# OpenBook_Reader_schematic.net
KiCad netlist of a schematic drawn in EAGLE
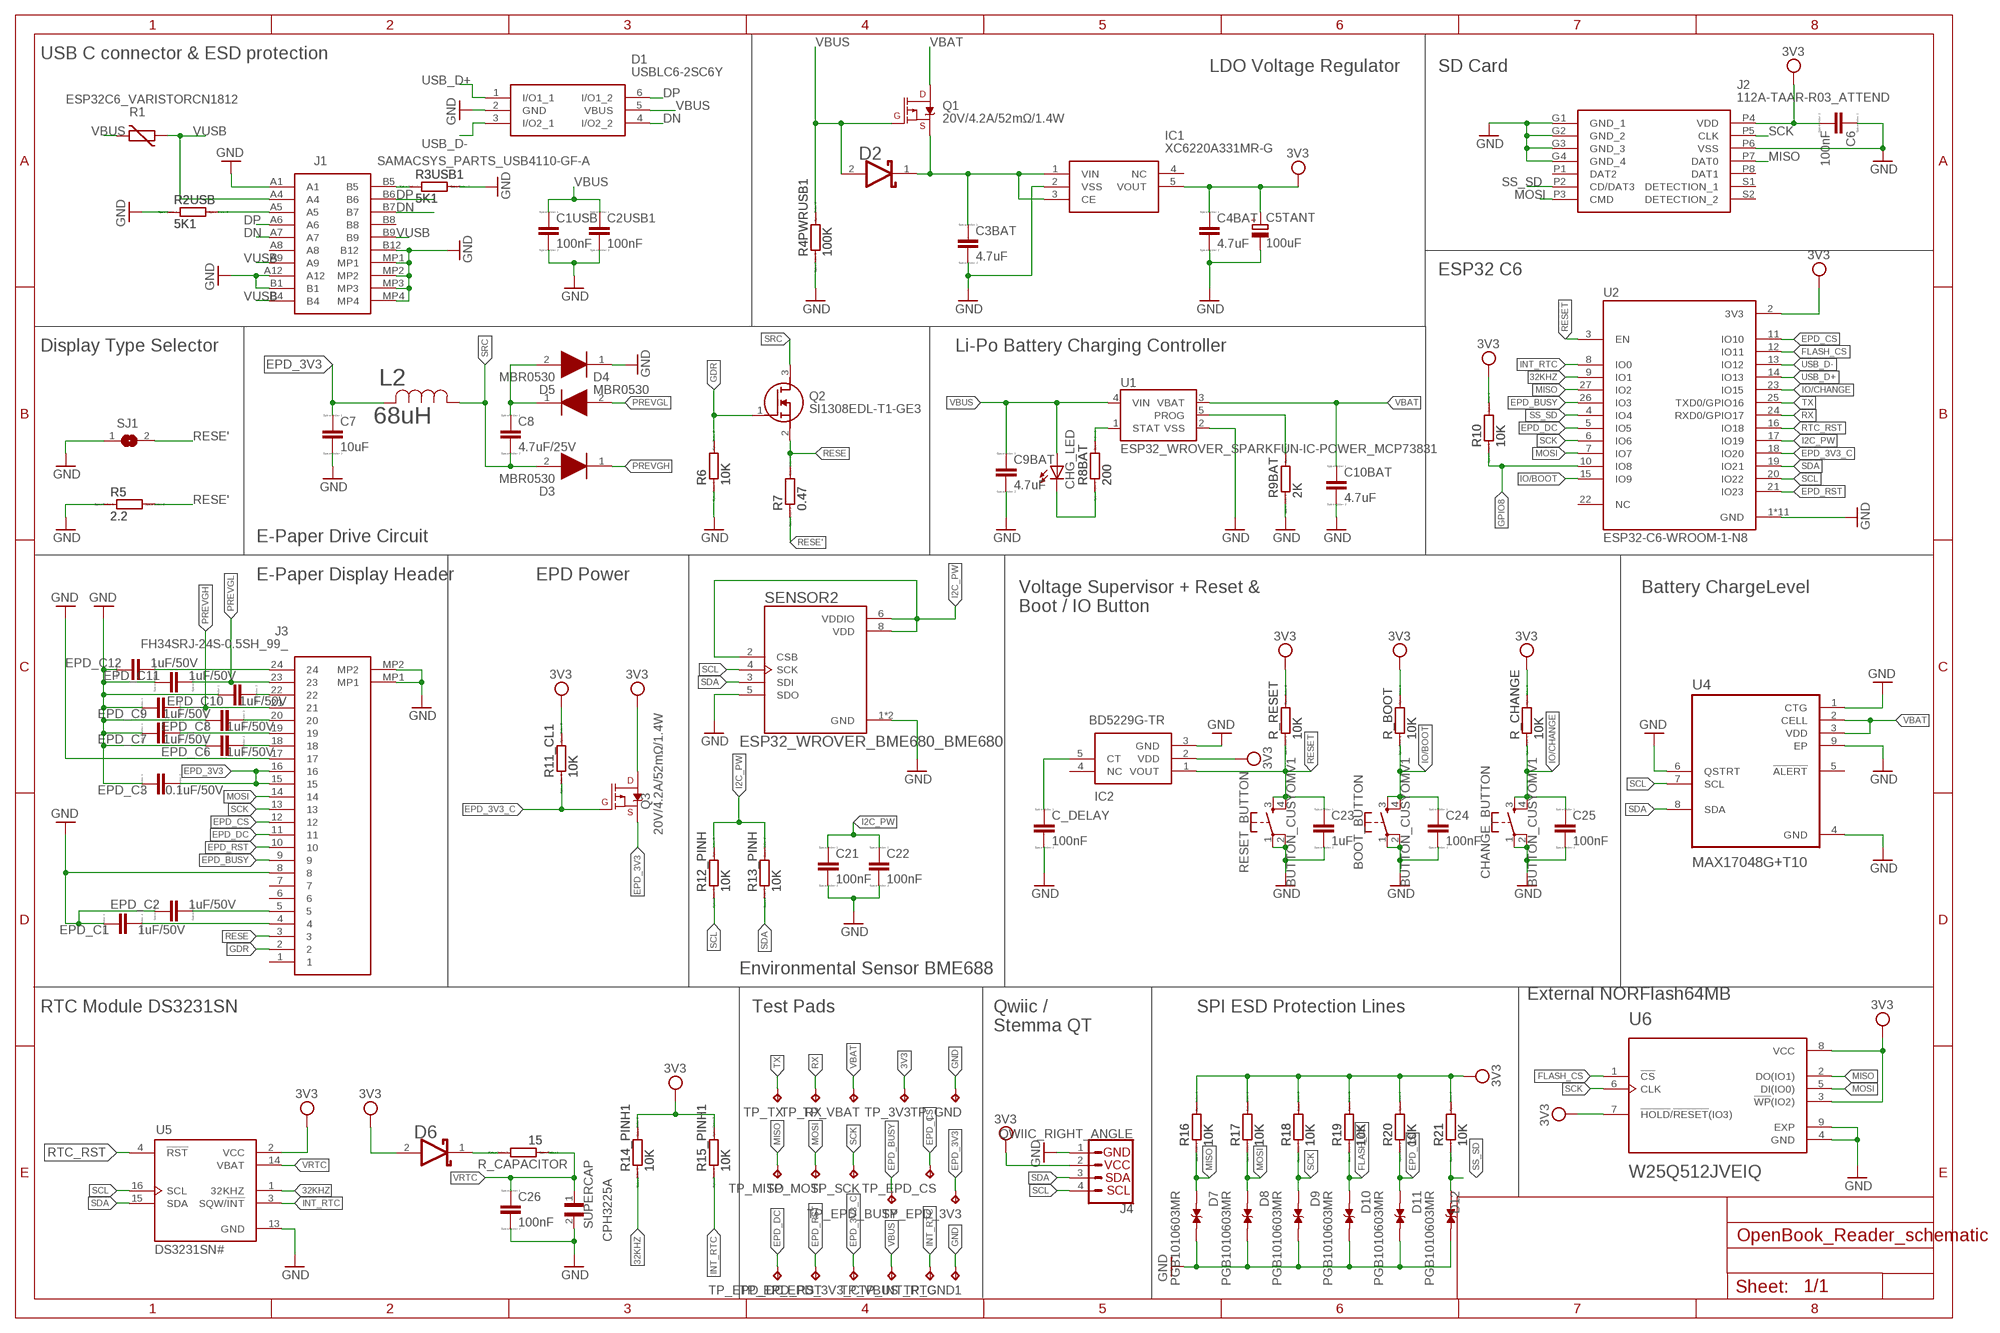
[diagram p0: schematic, sheet 1]

(export (version "E")
  (design (tool "Eeschema 10.0.6"))
  (components
    (comp (ref "BOOT_BUTTON")
      (value "BUTTON_CUSYOMV1")
      (footprint "eagle-import:MYBUTTON")
      (libsource (lib "eagle-import") (part "BUTTON_CUSYOMV1"))
    )
    (comp (ref "C1USB")
      (value "100nF")
      (footprint "eagle-import:ESP32_WROVER_EAGLE-LTSPICE_C0402")
      (libsource (lib "eagle-import") (part "EAGLE-LTSPICE_CC0402"))
    )
    (comp (ref "C2USB1")
      (value "100nF")
      (footprint "eagle-import:ESP32_WROVER_EAGLE-LTSPICE_C0402")
      (libsource (lib "eagle-import") (part "EAGLE-LTSPICE_CC0402"))
    )
    (comp (ref "C3BAT")
      (value "4.7uF")
      (footprint "eagle-import:ESP32_WROVER_EAGLE-LTSPICE_C0402")
      (libsource (lib "eagle-import") (part "EAGLE-LTSPICE_CC0402"))
    )
    (comp (ref "C4BAT")
      (value "4.7uF")
      (footprint "eagle-import:ESP32_WROVER_EAGLE-LTSPICE_C0402")
      (libsource (lib "eagle-import") (part "EAGLE-LTSPICE_CC0402"))
    )
    (comp (ref "C5TANT")
      (value "100uF")
      (footprint "eagle-import:RCL_CT3528")
      (libsource (lib "eagle-import") (part "RCL_CPOL-EUCT3528"))
    )
    (comp (ref "C6")
      (value "100nF")
      (footprint "eagle-import:ESP32_WROVER_EAGLE-LTSPICE_C0402")
      (libsource (lib "eagle-import") (part "EAGLE-LTSPICE_CC0402"))
    )
    (comp (ref "C7")
      (value "10uF")
      (footprint "eagle-import:ESP32_WROVER_EAGLE-LTSPICE_C0402")
      (libsource (lib "eagle-import") (part "EAGLE-LTSPICE_CC0402"))
    )
    (comp (ref "C8")
      (value "4.7uF/25V")
      (footprint "eagle-import:ESP32_WROVER_EAGLE-LTSPICE_C0402")
      (libsource (lib "eagle-import") (part "EAGLE-LTSPICE_CC0402"))
    )
    (comp (ref "C9BAT")
      (value "4.7uF")
      (footprint "eagle-import:ESP32_WROVER_EAGLE-LTSPICE_C0402")
      (libsource (lib "eagle-import") (part "EAGLE-LTSPICE_CC0402"))
    )
    (comp (ref "C10BAT")
      (value "4.7uF")
      (footprint "eagle-import:ESP32_WROVER_EAGLE-LTSPICE_C0402")
      (libsource (lib "eagle-import") (part "EAGLE-LTSPICE_CC0402"))
    )
    (comp (ref "C21")
      (value "100nF")
      (footprint "eagle-import:ESP32_WROVER_EAGLE-LTSPICE_C0402")
      (libsource (lib "eagle-import") (part "EAGLE-LTSPICE_CC0402"))
    )
    (comp (ref "C22")
      (value "100nF")
      (footprint "eagle-import:ESP32_WROVER_EAGLE-LTSPICE_C0402")
      (libsource (lib "eagle-import") (part "EAGLE-LTSPICE_CC0402"))
    )
    (comp (ref "C23")
      (value "1uF")
      (footprint "eagle-import:ESP32_WROVER_EAGLE-LTSPICE_C0402")
      (libsource (lib "eagle-import") (part "EAGLE-LTSPICE_CC0402"))
    )
    (comp (ref "C24")
      (value "100nF")
      (footprint "eagle-import:ESP32_WROVER_EAGLE-LTSPICE_C0402")
      (libsource (lib "eagle-import") (part "EAGLE-LTSPICE_CC0402"))
    )
    (comp (ref "C25")
      (value "100nF")
      (footprint "eagle-import:ESP32_WROVER_EAGLE-LTSPICE_C0402")
      (libsource (lib "eagle-import") (part "EAGLE-LTSPICE_CC0402"))
    )
    (comp (ref "C26")
      (value "100nF")
      (footprint "eagle-import:ESP32_WROVER_EAGLE-LTSPICE_C0402")
      (libsource (lib "eagle-import") (part "EAGLE-LTSPICE_CC0402"))
    )
    (comp (ref "CHANGE_BUTTON")
      (value "BUTTON_CUSYOMV1")
      (footprint "eagle-import:MYBUTTON")
      (libsource (lib "eagle-import") (part "BUTTON_CUSYOMV1"))
    )
    (comp (ref "CHG_LED")
      (value "ADAFRUIT_LEDCHIP-LED0603")
      (footprint "eagle-import:ADAFRUIT_CHIP-LED0603")
      (libsource (lib "eagle-import") (part "ADAFRUIT_LEDCHIP-LED0603"))
    )
    (comp (ref "C_DELAY")
      (value "100nF")
      (footprint "eagle-import:ESP32_WROVER_EAGLE-LTSPICE_C0402")
      (libsource (lib "eagle-import") (part "EAGLE-LTSPICE_CC0402"))
    )
    (comp (ref "D1")
      (value "USBLC6-2SC6Y")
      (footprint "eagle-import:SOT95P280X145-6N")
      (fields (field (name "MF") "STMicroelectronics"))
      (libsource (lib "eagle-import") (part "USBLC6-2SC6Y"))
    )
    (comp (ref "D2")
      (value "ESP32_WROVER_AVX---SD0805S020S1R0_AVX_SD0805S020S1R0_0_0AVX_SD0805S020S1R0_0_0")
      (footprint "eagle-import:ESP32_WROVER_AVX---SD0805S020S1R0_AVX_SD0805S020S1R0_0")
      (fields
        (field (name "DIGIKEY_PART_NUMBER") "478-7800-1-ND")
        (field (name "MF") "AVX")
        (field (name "MOUSER_PART_NUMBER") "581-SD0805S020S1R0")
      )
      (libsource (lib "eagle-import") (part "ESP32_WROVER_AVX---SD0805S020S1R0_AVX_SD0805S020S1R0_0_0AVX_SD0805S020S1R0_0_0"))
    )
    (comp (ref "D3")
      (value "MBR0530")
      (footprint "eagle-import:SOD3716X135N")
      (fields (field (name "MF") "ON Semiconductor"))
      (libsource (lib "eagle-import") (part "MBR0530"))
    )
    (comp (ref "D4")
      (value "MBR0530")
      (footprint "eagle-import:SOD3716X135N")
      (fields (field (name "MF") "ON Semiconductor"))
      (libsource (lib "eagle-import") (part "MBR0530"))
    )
    (comp (ref "D5")
      (value "MBR0530")
      (footprint "eagle-import:SOD3716X135N")
      (fields (field (name "MF") "ON Semiconductor"))
      (libsource (lib "eagle-import") (part "MBR0530"))
    )
    (comp (ref "D6")
      (value "ESP32_WROVER_AVX---SD0805S020S1R0_AVX_SD0805S020S1R0_0_0AVX_SD0805S020S1R0_0_0")
      (footprint "eagle-import:ESP32_WROVER_AVX---SD0805S020S1R0_AVX_SD0805S020S1R0_0")
      (fields
        (field (name "DIGIKEY_PART_NUMBER") "478-7800-1-ND")
        (field (name "MF") "AVX")
        (field (name "MOUSER_PART_NUMBER") "581-SD0805S020S1R0")
      )
      (libsource (lib "eagle-import") (part "ESP32_WROVER_AVX---SD0805S020S1R0_AVX_SD0805S020S1R0_0_0AVX_SD0805S020S1R0_0_0"))
    )
    (comp (ref "D7")
      (value "PGB1010603MR")
      (footprint "eagle-import:DIOC1608X36N")
      (fields (field (name "MF") "Littelfuse Inc."))
      (libsource (lib "eagle-import") (part "PGB1010603MR"))
    )
    (comp (ref "D8")
      (value "PGB1010603MR")
      (footprint "eagle-import:DIOC1608X36N")
      (fields (field (name "MF") "Littelfuse Inc."))
      (libsource (lib "eagle-import") (part "PGB1010603MR"))
    )
    (comp (ref "D9")
      (value "PGB1010603MR")
      (footprint "eagle-import:DIOC1608X36N")
      (fields (field (name "MF") "Littelfuse Inc."))
      (libsource (lib "eagle-import") (part "PGB1010603MR"))
    )
    (comp (ref "D10")
      (value "PGB1010603MR")
      (footprint "eagle-import:DIOC1608X36N")
      (fields (field (name "MF") "Littelfuse Inc."))
      (libsource (lib "eagle-import") (part "PGB1010603MR"))
    )
    (comp (ref "D11")
      (value "PGB1010603MR")
      (footprint "eagle-import:DIOC1608X36N")
      (fields (field (name "MF") "Littelfuse Inc."))
      (libsource (lib "eagle-import") (part "PGB1010603MR"))
    )
    (comp (ref "D12")
      (value "PGB1010603MR")
      (footprint "eagle-import:DIOC1608X36N")
      (fields (field (name "MF") "Littelfuse Inc."))
      (libsource (lib "eagle-import") (part "PGB1010603MR"))
    )
    (comp (ref "EPD_C1")
      (value "1uF/50V")
      (footprint "eagle-import:ESP32_WROVER_EAGLE-LTSPICE_C0402")
      (libsource (lib "eagle-import") (part "EAGLE-LTSPICE_CC0402"))
    )
    (comp (ref "EPD_C2")
      (value "1uF/50V")
      (footprint "eagle-import:ESP32_WROVER_EAGLE-LTSPICE_C0402")
      (libsource (lib "eagle-import") (part "EAGLE-LTSPICE_CC0402"))
    )
    (comp (ref "EPD_C3")
      (value "0.1uF/50V")
      (footprint "eagle-import:ESP32_WROVER_EAGLE-LTSPICE_C0402")
      (libsource (lib "eagle-import") (part "EAGLE-LTSPICE_CC0402"))
    )
    (comp (ref "EPD_C6")
      (value "1uF/50V")
      (footprint "eagle-import:ESP32_WROVER_EAGLE-LTSPICE_C0402")
      (libsource (lib "eagle-import") (part "EAGLE-LTSPICE_CC0402"))
    )
    (comp (ref "EPD_C7")
      (value "1uF/50V")
      (footprint "eagle-import:ESP32_WROVER_EAGLE-LTSPICE_C0402")
      (libsource (lib "eagle-import") (part "EAGLE-LTSPICE_CC0402"))
    )
    (comp (ref "EPD_C8")
      (value "1uF/50V")
      (footprint "eagle-import:ESP32_WROVER_EAGLE-LTSPICE_C0402")
      (libsource (lib "eagle-import") (part "EAGLE-LTSPICE_CC0402"))
    )
    (comp (ref "EPD_C9")
      (value "1uF/50V")
      (footprint "eagle-import:ESP32_WROVER_EAGLE-LTSPICE_C0402")
      (libsource (lib "eagle-import") (part "EAGLE-LTSPICE_CC0402"))
    )
    (comp (ref "EPD_C10")
      (value "1uF/50V")
      (footprint "eagle-import:ESP32_WROVER_EAGLE-LTSPICE_C0402")
      (libsource (lib "eagle-import") (part "EAGLE-LTSPICE_CC0402"))
    )
    (comp (ref "EPD_C11")
      (value "1uF/50V")
      (footprint "eagle-import:ESP32_WROVER_EAGLE-LTSPICE_C0402")
      (libsource (lib "eagle-import") (part "EAGLE-LTSPICE_CC0402"))
    )
    (comp (ref "EPD_C12")
      (value "1uF/50V")
      (footprint "eagle-import:ESP32_WROVER_EAGLE-LTSPICE_C0402")
      (libsource (lib "eagle-import") (part "EAGLE-LTSPICE_CC0402"))
    )
    (comp (ref "IC1")
      (value "XC6220A331MR-G")
      (footprint "eagle-import:SOT95P280X120-5N")
      (fields (field (name "MOUSER_PART_NUMBER") "865-XC6220A331MR-G"))
      (libsource (lib "eagle-import") (part "XC6220A331MR-G"))
    )
    (comp (ref "IC2")
      (value "BD5229G-TR")
      (footprint "eagle-import:SOT95P280X125-5N")
      (fields (field (name "MOUSER_PART_NUMBER") "755-BD5229G-TR"))
      (libsource (lib "eagle-import") (part "BD5229G-TR"))
    )
    (comp (ref "J1")
      (value "SAMACSYS_PARTS_USB4110-GF-A")
      (footprint "eagle-import:SAMACSYS_PARTS_USB4110GFA")
      (fields
        (field (name "MANUFACTURER_PART_NUMBER") "USB4110-GF-A")
        (field (name "MOUSER_PART_NUMBER") "640-USB4110-GF-A")
      )
      (libsource (lib "eagle-import") (part "SAMACSYS_PARTS_USB4110-GF-A"))
    )
    (comp (ref "J2")
      (value "112A-TAAR-R03_ATTEND")
      (footprint "eagle-import:112ATAARR03ATTEND")
      (fields (field (name "MANUFACTURER_PART_NUMBER") "112A-TAAR-R03 ATTEND"))
      (libsource (lib "eagle-import") (part "112A-TAAR-R03_ATTEND"))
    )
    (comp (ref "J3")
      (value "FH34SRJ-24S-0.5SH_99_")
      (footprint "eagle-import:FH34SRJ24S05SH99")
      (fields
        (field (name "MANUFACTURER_PART_NUMBER") "FH34SRJ-24S-0.5SH(99)")
        (field (name "MOUSER_PART_NUMBER") "798-FH34SRJ24S05SH99")
      )
      (libsource (lib "eagle-import") (part "FH34SRJ-24S-0.5SH_99_"))
    )
    (comp (ref "J4")
      (value "QWIIC_RIGHT_ANGLE")
      (footprint "eagle-import:JST04_1MM_RA")
      (libsource (lib "eagle-import") (part "QWIIC_CONNECTORJS-1MM"))
    )
    (comp (ref "L2")
      (value "68uH")
      (footprint "eagle-import:IND_4828-WE-TPC_WRE")
      (fields
        (field (name "MANUFACTURER_PART_NUMBER") "744043680")
        (field (name "COPYRIGHT") "Copyright (C) 2024 Ultra Librarian. All rights reserved.")
      )
      (libsource (lib "eagle-import") (part "744043680IND_4828-WE-TPC_WRE"))
    )
    (comp (ref "Q1")
      (value "20V/4.2A/52mΩ/1.4W")
      (footprint "eagle-import:ESP32_WROVER_SPARKFUN-DISCRETESEMI_SOT23-3")
      (libsource (lib "eagle-import") (part "ESP32_WROVER_SPARKFUN-DISCRETESEMI_MOSFET_PCH-DMG2305UX-7"))
    )
    (comp (ref "Q2")
      (value "SI1308EDL-T1-GE3")
      (footprint "eagle-import:SOT65P210X110-3N")
      (fields (field (name "MF") "Vishay Siliconix"))
      (libsource (lib "eagle-import") (part "SI1308EDL-T1-GE3"))
    )
    (comp (ref "Q3")
      (value "20V/4.2A/52mΩ/1.4W")
      (footprint "eagle-import:ESP32_WROVER_SPARKFUN-DISCRETESEMI_SOT23-3")
      (libsource (lib "eagle-import") (part "ESP32_WROVER_SPARKFUN-DISCRETESEMI_MOSFET_PCH-DMG2305UX-7"))
    )
    (comp (ref "R1")
      (value "ESP32C6_VARISTORCN1812")
      (footprint "eagle-import:ESP32C6_VARISTOR_CT_CN1812")
      (libsource (lib "eagle-import") (part "ESP32C6_VARISTORCN1812"))
    )
    (comp (ref "R2USB")
      (value "5K1")
      (footprint "eagle-import:ESP32_WROVER_EAGLE-LTSPICE_R0402")
      (libsource (lib "eagle-import") (part "ESP32_WROVER_EAGLE-LTSPICE_RR0402"))
    )
    (comp (ref "R3USB1")
      (value "5K1")
      (footprint "eagle-import:ESP32_WROVER_EAGLE-LTSPICE_R0402")
      (libsource (lib "eagle-import") (part "ESP32_WROVER_EAGLE-LTSPICE_RR0402"))
    )
    (comp (ref "R4PWRUSB1")
      (value "100K")
      (footprint "eagle-import:ESP32_WROVER_EAGLE-LTSPICE_R0402")
      (libsource (lib "eagle-import") (part "ESP32_WROVER_EAGLE-LTSPICE_RR0402"))
    )
    (comp (ref "R5")
      (value "2.2")
      (footprint "eagle-import:ESP32_WROVER_EAGLE-LTSPICE_R0402")
      (libsource (lib "eagle-import") (part "ESP32_WROVER_EAGLE-LTSPICE_RR0402"))
    )
    (comp (ref "R6")
      (value "10K")
      (footprint "eagle-import:ESP32_WROVER_EAGLE-LTSPICE_R0402")
      (libsource (lib "eagle-import") (part "ESP32_WROVER_EAGLE-LTSPICE_RR0402"))
    )
    (comp (ref "R7")
      (value "0.47")
      (footprint "eagle-import:ESP32_WROVER_EAGLE-LTSPICE_R0402")
      (libsource (lib "eagle-import") (part "ESP32_WROVER_EAGLE-LTSPICE_RR0402"))
    )
    (comp (ref "R8BAT")
      (value "200")
      (footprint "eagle-import:ESP32_WROVER_EAGLE-LTSPICE_R0402")
      (libsource (lib "eagle-import") (part "ESP32_WROVER_EAGLE-LTSPICE_RR0402"))
    )
    (comp (ref "R9BAT")
      (value "2K")
      (footprint "eagle-import:ESP32_WROVER_EAGLE-LTSPICE_R0402")
      (libsource (lib "eagle-import") (part "ESP32_WROVER_EAGLE-LTSPICE_RR0402"))
    )
    (comp (ref "R10")
      (value "10K")
      (footprint "eagle-import:ESP32_WROVER_EAGLE-LTSPICE_R0402")
      (libsource (lib "eagle-import") (part "ESP32_WROVER_EAGLE-LTSPICE_RR0402"))
    )
    (comp (ref "R11_CL1")
      (value "10K")
      (footprint "eagle-import:ESP32_WROVER_EAGLE-LTSPICE_R0402")
      (libsource (lib "eagle-import") (part "ESP32_WROVER_EAGLE-LTSPICE_RR0402"))
    )
    (comp (ref "R12_PINH")
      (value "10K")
      (footprint "eagle-import:ESP32_WROVER_EAGLE-LTSPICE_R0402")
      (libsource (lib "eagle-import") (part "ESP32_WROVER_EAGLE-LTSPICE_RR0402"))
    )
    (comp (ref "R13_PINH")
      (value "10K")
      (footprint "eagle-import:ESP32_WROVER_EAGLE-LTSPICE_R0402")
      (libsource (lib "eagle-import") (part "ESP32_WROVER_EAGLE-LTSPICE_RR0402"))
    )
    (comp (ref "R14_PINH1")
      (value "10K")
      (footprint "eagle-import:ESP32_WROVER_EAGLE-LTSPICE_R0402")
      (libsource (lib "eagle-import") (part "ESP32_WROVER_EAGLE-LTSPICE_RR0402"))
    )
    (comp (ref "R15_PINH1")
      (value "10K")
      (footprint "eagle-import:ESP32_WROVER_EAGLE-LTSPICE_R0402")
      (libsource (lib "eagle-import") (part "ESP32_WROVER_EAGLE-LTSPICE_RR0402"))
    )
    (comp (ref "R16")
      (value "10K")
      (footprint "eagle-import:ESP32_WROVER_EAGLE-LTSPICE_R0402")
      (libsource (lib "eagle-import") (part "ESP32_WROVER_EAGLE-LTSPICE_RR0402"))
    )
    (comp (ref "R17")
      (value "10K")
      (footprint "eagle-import:ESP32_WROVER_EAGLE-LTSPICE_R0402")
      (libsource (lib "eagle-import") (part "ESP32_WROVER_EAGLE-LTSPICE_RR0402"))
    )
    (comp (ref "R18")
      (value "10K")
      (footprint "eagle-import:ESP32_WROVER_EAGLE-LTSPICE_R0402")
      (libsource (lib "eagle-import") (part "ESP32_WROVER_EAGLE-LTSPICE_RR0402"))
    )
    (comp (ref "R19")
      (value "10K")
      (footprint "eagle-import:ESP32_WROVER_EAGLE-LTSPICE_R0402")
      (libsource (lib "eagle-import") (part "ESP32_WROVER_EAGLE-LTSPICE_RR0402"))
    )
    (comp (ref "R20")
      (value "10K")
      (footprint "eagle-import:ESP32_WROVER_EAGLE-LTSPICE_R0402")
      (libsource (lib "eagle-import") (part "ESP32_WROVER_EAGLE-LTSPICE_RR0402"))
    )
    (comp (ref "R21")
      (value "10K")
      (footprint "eagle-import:ESP32_WROVER_EAGLE-LTSPICE_R0402")
      (libsource (lib "eagle-import") (part "ESP32_WROVER_EAGLE-LTSPICE_RR0402"))
    )
    (comp (ref "RESET_BUTTON")
      (value "BUTTON_CUSYOMV1")
      (footprint "eagle-import:MYBUTTON")
      (libsource (lib "eagle-import") (part "BUTTON_CUSYOMV1"))
    )
    (comp (ref "R_BOOT")
      (value "10K")
      (footprint "eagle-import:ESP32_WROVER_EAGLE-LTSPICE_R0402")
      (libsource (lib "eagle-import") (part "ESP32_WROVER_EAGLE-LTSPICE_RR0402"))
    )
    (comp (ref "R_CAPACITOR")
      (value "15")
      (footprint "eagle-import:ESP32_WROVER_EAGLE-LTSPICE_R0402")
      (libsource (lib "eagle-import") (part "ESP32_WROVER_EAGLE-LTSPICE_RR0402"))
    )
    (comp (ref "R_CHANGE")
      (value "10K")
      (footprint "eagle-import:ESP32_WROVER_EAGLE-LTSPICE_R0402")
      (libsource (lib "eagle-import") (part "ESP32_WROVER_EAGLE-LTSPICE_RR0402"))
    )
    (comp (ref "R_RESET")
      (value "10K")
      (footprint "eagle-import:ESP32_WROVER_EAGLE-LTSPICE_R0402")
      (libsource (lib "eagle-import") (part "ESP32_WROVER_EAGLE-LTSPICE_RR0402"))
    )
    (comp (ref "SENSOR2")
      (value "ESP32_WROVER_BME680_BME680")
      (footprint "eagle-import:ESP32_WROVER_BME680_PSON80P300X300X100-8N")
      (fields (field (name "MF") "Bosch Sensortec") (field (name "MP") "BME680"))
      (libsource (lib "eagle-import") (part "ESP32_WROVER_BME680_BME680"))
    )
    (comp (ref "SJ1") (value "SJ") (footprint "eagle-import:SJ") (libsource (lib "eagle-import") (part "SJ")))
    (comp (ref "SUPERCAP")
      (value "CPH3225A")
      (footprint "eagle-import:CAPCP3225X100N")
      (fields (field (name "MF") "Seiko Instruments"))
      (libsource (lib "eagle-import") (part "CPH3225A"))
    )
    (comp (ref "TP_3V3")
      (value "TPTP20R")
      (footprint "eagle-import:TP20R")
      (libsource (lib "eagle-import") (part "TPTP20R"))
    )
    (comp (ref "TP_EPD_3V3")
      (value "TPTP20R")
      (footprint "eagle-import:TP20R")
      (libsource (lib "eagle-import") (part "TPTP20R"))
    )
    (comp (ref "TP_EPD_3V3_C")
      (value "TPTP20R")
      (footprint "eagle-import:TP20R")
      (libsource (lib "eagle-import") (part "TPTP20R"))
    )
    (comp (ref "TP_EPD_BUSY")
      (value "TPTP20R")
      (footprint "eagle-import:TP20R")
      (libsource (lib "eagle-import") (part "TPTP20R"))
    )
    (comp (ref "TP_EPD_CS")
      (value "TPTP20R")
      (footprint "eagle-import:TP20R")
      (libsource (lib "eagle-import") (part "TPTP20R"))
    )
    (comp (ref "TP_EPD_DC")
      (value "TPTP20R")
      (footprint "eagle-import:TP20R")
      (libsource (lib "eagle-import") (part "TPTP20R"))
    )
    (comp (ref "TP_EPD_RST")
      (value "TPTP20R")
      (footprint "eagle-import:TP20R")
      (libsource (lib "eagle-import") (part "TPTP20R"))
    )
    (comp (ref "TP_GND")
      (value "TPTP20R")
      (footprint "eagle-import:TP20R")
      (libsource (lib "eagle-import") (part "TPTP20R"))
    )
    (comp (ref "TP_GND1")
      (value "TPTP20R")
      (footprint "eagle-import:TP20R")
      (libsource (lib "eagle-import") (part "TPTP20R"))
    )
    (comp (ref "TP_INT_RTC")
      (value "TPTP20R")
      (footprint "eagle-import:TP20R")
      (libsource (lib "eagle-import") (part "TPTP20R"))
    )
    (comp (ref "TP_MISO")
      (value "TPTP20R")
      (footprint "eagle-import:TP20R")
      (libsource (lib "eagle-import") (part "TPTP20R"))
    )
    (comp (ref "TP_MOSI")
      (value "TPTP20R")
      (footprint "eagle-import:TP20R")
      (libsource (lib "eagle-import") (part "TPTP20R"))
    )
    (comp (ref "TP_RX")
      (value "TPTP20R")
      (footprint "eagle-import:TP20R")
      (libsource (lib "eagle-import") (part "TPTP20R"))
    )
    (comp (ref "TP_SCK")
      (value "TPTP20R")
      (footprint "eagle-import:TP20R")
      (libsource (lib "eagle-import") (part "TPTP20R"))
    )
    (comp (ref "TP_TX")
      (value "TPTP20R")
      (footprint "eagle-import:TP20R")
      (libsource (lib "eagle-import") (part "TPTP20R"))
    )
    (comp (ref "TP_VBAT")
      (value "TPTP20R")
      (footprint "eagle-import:TP20R")
      (libsource (lib "eagle-import") (part "TPTP20R"))
    )
    (comp (ref "TP_VBUS")
      (value "TPTP20R")
      (footprint "eagle-import:TP20R")
      (libsource (lib "eagle-import") (part "TPTP20R"))
    )
    (comp (ref "U1")
      (value "ESP32_WROVER_SPARKFUN-IC-POWER_MCP73831")
      (footprint "eagle-import:ESP32_WROVER_SPARKFUN-IC-POWER_SOT23-5")
      (libsource (lib "eagle-import") (part "ESP32_WROVER_SPARKFUN-IC-POWER_MCP73831"))
    )
    (comp (ref "U2")
      (value "ESP32-C6-WROOM-1-N8")
      (footprint "eagle-import:XCVR_ESP32-C6-WROOM-1-N8")
      (fields (field (name "MF") "Espressif Systems"))
      (libsource (lib "eagle-import") (part "ESP32-C6-WROOM-1-N8"))
    )
    (comp (ref "U4")
      (value "MAX17048G+T10")
      (footprint "eagle-import:SON50P200X200X80-9N")
      (fields (field (name "MF") "Analog Devices"))
      (libsource (lib "eagle-import") (part "MAX17048G+T10"))
    )
    (comp (ref "U5")
      (value "DS3231SN#")
      (footprint "eagle-import:SOIC127P1032X265-16N")
      (fields (field (name "MF") "Analog Devices"))
      (libsource (lib "eagle-import") (part "DS3231SN#"))
    )
    (comp (ref "U6")
      (value "W25Q512JVEIQ")
      (footprint "eagle-import:SON127P600X800X80-9N")
      (fields (field (name "MF") "Winbond Electronics"))
      (libsource (lib "eagle-import") (part "W25Q512JVEIQ"))
    )
  )
  (nets
    (net (code "1") (name "/DN") (class "Default")
      (node (ref "D1") (pin "4") (pinfunction "I/O2_2_4") (pintype "bidirectional"))
      (node (ref "J1") (pin "A7") (pinfunction "A7_A7") (pintype "bidirectional"))
      (node (ref "J1") (pin "B7") (pinfunction "B7_B7") (pintype "bidirectional"))
    )
    (net (code "2") (name "/DP") (class "Default")
      (node (ref "D1") (pin "6") (pinfunction "I/O1_2_6") (pintype "bidirectional"))
      (node (ref "J1") (pin "A6") (pinfunction "A6_A6") (pintype "bidirectional"))
      (node (ref "J1") (pin "B6") (pinfunction "B6_B6") (pintype "bidirectional"))
    )
    (net (code "3") (name "/VUSB") (class "Default")
      (node (ref "J1") (pin "A4") (pinfunction "A4_A4") (pintype "bidirectional"))
      (node (ref "J1") (pin "A9") (pinfunction "A9_A9") (pintype "bidirectional"))
      (node (ref "J1") (pin "B4") (pinfunction "B4_B4") (pintype "bidirectional"))
      (node (ref "J1") (pin "B9") (pinfunction "B9_B9") (pintype "bidirectional"))
      (node (ref "R1") (pin "1") (pinfunction "1_1") (pintype "passive"))
    )
    (net (code "4") (name "3V3") (class "Default")
      (node (ref "C4BAT") (pin "1") (pinfunction "1_1") (pintype "passive"))
      (node (ref "C5TANT") (pin "+") (pinfunction "+_+") (pintype "passive"))
      (node (ref "C6") (pin "2") (pinfunction "2_2") (pintype "passive"))
      (node (ref "D6") (pin "2") (pinfunction "ANODE_2") (pintype "bidirectional"))
      (node (ref "IC1") (pin "5") (pinfunction "VOUT_5") (pintype "bidirectional"))
      (node (ref "IC2") (pin "2") (pinfunction "VDD_2") (pintype "bidirectional"))
      (node (ref "J2") (pin "P4") (pinfunction "VDD_P4") (pintype "bidirectional"))
      (node (ref "J4") (pin "2") (pinfunction "2_2") (pintype "power_in"))
      (node (ref "Q3") (pin "3") (pinfunction "D_3") (pintype "bidirectional"))
      (node (ref "R10") (pin "2") (pinfunction "2_2") (pintype "passive"))
      (node (ref "R11_CL1") (pin "2") (pinfunction "2_2") (pintype "passive"))
      (node (ref "R14_PINH1") (pin "2") (pinfunction "2_2") (pintype "passive"))
      (node (ref "R15_PINH1") (pin "2") (pinfunction "2_2") (pintype "passive"))
      (node (ref "R16") (pin "2") (pinfunction "2_2") (pintype "passive"))
      (node (ref "R17") (pin "2") (pinfunction "2_2") (pintype "passive"))
      (node (ref "R18") (pin "2") (pinfunction "2_2") (pintype "passive"))
      (node (ref "R19") (pin "2") (pinfunction "2_2") (pintype "passive"))
      (node (ref "R20") (pin "2") (pinfunction "2_2") (pintype "passive"))
      (node (ref "R21") (pin "2") (pinfunction "2_2") (pintype "passive"))
      (node (ref "R_BOOT") (pin "2") (pinfunction "2_2") (pintype "passive"))
      (node (ref "R_CHANGE") (pin "2") (pinfunction "2_2") (pintype "passive"))
      (node (ref "R_RESET") (pin "2") (pinfunction "2_2") (pintype "passive"))
      (node (ref "TP_3V3") (pin "TP") (pinfunction "TP_TP") (pintype "input"))
      (node (ref "U2") (pin "2") (pinfunction "3V3_2") (pintype "power_in"))
      (node (ref "U5") (pin "2") (pinfunction "VCC_2") (pintype "power_in"))
      (node (ref "U6") (pin "3") (pinfunction "~{WP}(IO2)_3") (pintype "bidirectional"))
      (node (ref "U6") (pin "7") (pinfunction "~{HOLD}/~{RESET}(IO3)_7") (pintype "bidirectional"))
      (node (ref "U6") (pin "8") (pinfunction "VCC_8") (pintype "power_in"))
    )
    (net (code "5") (name "32KHZ") (class "Default")
      (node (ref "R14_PINH1") (pin "1") (pinfunction "1_1") (pintype "passive"))
      (node (ref "U2") (pin "9") (pinfunction "IO1_9") (pintype "bidirectional"))
      (node (ref "U5") (pin "1") (pinfunction "32KHZ_1") (pintype "output"))
    )
    (net (code "6") (name "EPD_3V3") (class "Default")
      (node (ref "C7") (pin "1") (pinfunction "1_1") (pintype "passive"))
      (node (ref "EPD_C3") (pin "2") (pinfunction "2_2") (pintype "passive"))
      (node (ref "J3") (pin "15") (pinfunction "15_15") (pintype "bidirectional"))
      (node (ref "J3") (pin "16") (pinfunction "16_16") (pintype "bidirectional"))
      (node (ref "L2") (pin "2") (pinfunction "2_2") (pintype "passive"))
      (node (ref "Q3") (pin "2") (pinfunction "S_2") (pintype "bidirectional"))
      (node (ref "TP_EPD_3V3") (pin "TP") (pinfunction "TP_TP") (pintype "input"))
    )
    (net (code "7") (name "EPD_3V3_C") (class "Default")
      (node (ref "Q3") (pin "1") (pinfunction "G_1") (pintype "bidirectional"))
      (node (ref "R11_CL1") (pin "1") (pinfunction "1_1") (pintype "passive"))
      (node (ref "TP_EPD_3V3_C") (pin "TP") (pinfunction "TP_TP") (pintype "input"))
      (node (ref "U2") (pin "18") (pinfunction "IO20_18") (pintype "bidirectional"))
    )
    (net (code "8") (name "EPD_BUSY") (class "Default")
      (node (ref "J3") (pin "9") (pinfunction "9_9") (pintype "bidirectional"))
      (node (ref "TP_EPD_BUSY") (pin "TP") (pinfunction "TP_TP") (pintype "input"))
      (node (ref "U2") (pin "26") (pinfunction "IO3_26") (pintype "bidirectional"))
    )
    (net (code "9") (name "EPD_CS") (class "Default")
      (node (ref "D11") (pin "1") (pinfunction "1_1") (pintype "passive"))
      (node (ref "J3") (pin "12") (pinfunction "12_12") (pintype "bidirectional"))
      (node (ref "R20") (pin "1") (pinfunction "1_1") (pintype "passive"))
      (node (ref "TP_EPD_CS") (pin "TP") (pinfunction "TP_TP") (pintype "input"))
      (node (ref "U2") (pin "11") (pinfunction "IO10_11") (pintype "bidirectional"))
    )
    (net (code "10") (name "EPD_DC") (class "Default")
      (node (ref "J3") (pin "11") (pinfunction "11_11") (pintype "bidirectional"))
      (node (ref "TP_EPD_DC") (pin "TP") (pinfunction "TP_TP") (pintype "input"))
      (node (ref "U2") (pin "5") (pinfunction "IO5_5") (pintype "bidirectional"))
    )
    (net (code "11") (name "EPD_RST") (class "Default")
      (node (ref "J3") (pin "10") (pinfunction "10_10") (pintype "bidirectional"))
      (node (ref "TP_EPD_RST") (pin "TP") (pinfunction "TP_TP") (pintype "input"))
      (node (ref "U2") (pin "21") (pinfunction "IO23_21") (pintype "bidirectional"))
    )
    (net (code "12") (name "FLASH_CS") (class "Default")
      (node (ref "D10") (pin "1") (pinfunction "1_1") (pintype "passive"))
      (node (ref "R19") (pin "1") (pinfunction "1_1") (pintype "passive"))
      (node (ref "U2") (pin "12") (pinfunction "IO11_12") (pintype "bidirectional"))
      (node (ref "U6") (pin "1") (pinfunction "~{CS}_1") (pintype "input"))
    )
    (net (code "13") (name "GDR") (class "Default")
      (node (ref "J3") (pin "2") (pinfunction "2_2") (pintype "bidirectional"))
      (node (ref "Q2") (pin "1") (pinfunction "G_1") (pintype "bidirectional"))
      (node (ref "R6") (pin "2") (pinfunction "2_2") (pintype "passive"))
    )
    (net (code "14") (name "GND") (class "Default")
      (node (ref "BOOT_BUTTON") (pin "1") (pinfunction "1_1") (pintype "passive"))
      (node (ref "BOOT_BUTTON") (pin "2") (pinfunction "2_2") (pintype "passive"))
      (node (ref "C10BAT") (pin "2") (pinfunction "2_2") (pintype "passive"))
      (node (ref "C1USB") (pin "2") (pinfunction "2_2") (pintype "passive"))
      (node (ref "C21") (pin "2") (pinfunction "2_2") (pintype "passive"))
      (node (ref "C22") (pin "2") (pinfunction "2_2") (pintype "passive"))
      (node (ref "C23") (pin "2") (pinfunction "2_2") (pintype "passive"))
      (node (ref "C24") (pin "2") (pinfunction "2_2") (pintype "passive"))
      (node (ref "C25") (pin "2") (pinfunction "2_2") (pintype "passive"))
      (node (ref "C26") (pin "2") (pinfunction "2_2") (pintype "passive"))
      (node (ref "C2USB1") (pin "2") (pinfunction "2_2") (pintype "passive"))
      (node (ref "C3BAT") (pin "2") (pinfunction "2_2") (pintype "passive"))
      (node (ref "C4BAT") (pin "2") (pinfunction "2_2") (pintype "passive"))
      (node (ref "C5TANT") (pin "-") (pinfunction "-_-") (pintype "passive"))
      (node (ref "C6") (pin "1") (pinfunction "1_1") (pintype "passive"))
      (node (ref "C7") (pin "2") (pinfunction "2_2") (pintype "passive"))
      (node (ref "C9BAT") (pin "2") (pinfunction "2_2") (pintype "passive"))
      (node (ref "CHANGE_BUTTON") (pin "1") (pinfunction "1_1") (pintype "passive"))
      (node (ref "CHANGE_BUTTON") (pin "2") (pinfunction "2_2") (pintype "passive"))
      (node (ref "C_DELAY") (pin "2") (pinfunction "2_2") (pintype "passive"))
      (node (ref "D1") (pin "2") (pinfunction "GND_2") (pintype "bidirectional"))
      (node (ref "D10") (pin "2") (pinfunction "2_2") (pintype "passive"))
      (node (ref "D11") (pin "2") (pinfunction "2_2") (pintype "passive"))
      (node (ref "D12") (pin "2") (pinfunction "2_2") (pintype "passive"))
      (node (ref "D5") (pin "1") (pinfunction "K_1") (pintype "bidirectional"))
      (node (ref "D7") (pin "2") (pinfunction "2_2") (pintype "passive"))
      (node (ref "D8") (pin "2") (pinfunction "2_2") (pintype "passive"))
      (node (ref "D9") (pin "2") (pinfunction "2_2") (pintype "passive"))
      (node (ref "EPD_C1") (pin "1") (pinfunction "1_1") (pintype "passive"))
      (node (ref "EPD_C10") (pin "1") (pinfunction "1_1") (pintype "passive"))
      (node (ref "EPD_C11") (pin "1") (pinfunction "1_1") (pintype "passive"))
      (node (ref "EPD_C12") (pin "1") (pinfunction "1_1") (pintype "passive"))
      (node (ref "EPD_C2") (pin "1") (pinfunction "1_1") (pintype "passive"))
      (node (ref "EPD_C3") (pin "1") (pinfunction "1_1") (pintype "passive"))
      (node (ref "EPD_C6") (pin "1") (pinfunction "1_1") (pintype "passive"))
      (node (ref "EPD_C7") (pin "1") (pinfunction "1_1") (pintype "passive"))
      (node (ref "EPD_C8") (pin "1") (pinfunction "1_1") (pintype "passive"))
      (node (ref "EPD_C9") (pin "1") (pinfunction "1_1") (pintype "passive"))
      (node (ref "IC1") (pin "2") (pinfunction "VSS_2") (pintype "bidirectional"))
      (node (ref "IC2") (pin "3") (pinfunction "GND_3") (pintype "bidirectional"))
      (node (ref "J1") (pin "A1") (pinfunction "A1_A1") (pintype "bidirectional"))
      (node (ref "J1") (pin "A12") (pinfunction "A12_A12") (pintype "bidirectional"))
      (node (ref "J1") (pin "B1") (pinfunction "B1_B1") (pintype "bidirectional"))
      (node (ref "J1") (pin "B12") (pinfunction "B12_B12") (pintype "bidirectional"))
      (node (ref "J1") (pin "MP1") (pinfunction "MP1_MP1") (pintype "bidirectional"))
      (node (ref "J1") (pin "MP2") (pinfunction "MP2_MP2") (pintype "bidirectional"))
      (node (ref "J1") (pin "MP3") (pinfunction "MP3_MP3") (pintype "bidirectional"))
      (node (ref "J1") (pin "MP4") (pinfunction "MP4_MP4") (pintype "bidirectional"))
      (node (ref "J2") (pin "G1") (pinfunction "GND_1_G1") (pintype "bidirectional"))
      (node (ref "J2") (pin "G2") (pinfunction "GND_2_G2") (pintype "bidirectional"))
      (node (ref "J2") (pin "G3") (pinfunction "GND_3_G3") (pintype "bidirectional"))
      (node (ref "J2") (pin "G4") (pinfunction "GND_4_G4") (pintype "bidirectional"))
      (node (ref "J2") (pin "P6") (pinfunction "VSS_P6") (pintype "bidirectional"))
      (node (ref "J3") (pin "17") (pinfunction "17_17") (pintype "bidirectional"))
      (node (ref "J3") (pin "8") (pinfunction "8_8") (pintype "bidirectional"))
      (node (ref "J3") (pin "MP1") (pinfunction "MP1_MP1") (pintype "bidirectional"))
      (node (ref "J3") (pin "MP2") (pinfunction "MP2_MP2") (pintype "bidirectional"))
      (node (ref "J4") (pin "1") (pinfunction "1_1") (pintype "power_in"))
      (node (ref "R2USB") (pin "1") (pinfunction "1_1") (pintype "passive"))
      (node (ref "R3USB1") (pin "2") (pinfunction "2_2") (pintype "passive"))
      (node (ref "R4PWRUSB1") (pin "1") (pinfunction "1_1") (pintype "passive"))
      (node (ref "R5") (pin "1") (pinfunction "1_1") (pintype "passive"))
      (node (ref "R6") (pin "1") (pinfunction "1_1") (pintype "passive"))
      (node (ref "R9BAT") (pin "1") (pinfunction "1_1") (pintype "passive"))
      (node (ref "RESET_BUTTON") (pin "1") (pinfunction "1_1") (pintype "passive"))
      (node (ref "RESET_BUTTON") (pin "2") (pinfunction "2_2") (pintype "passive"))
      (node (ref "SENSOR2") (pin "1") (pinfunction "GND_1") (pintype "power_in"))
      (node (ref "SENSOR2") (pin "5") (pinfunction "SDO_5") (pintype "bidirectional"))
      (node (ref "SENSOR2") (pin "7") (pinfunction "GND_7") (pintype "power_in"))
      (node (ref "SJ1") (pin "1") (pinfunction "1_1") (pintype "passive"))
      (node (ref "SUPERCAP") (pin "2") (pinfunction "2_2") (pintype "passive"))
      (node (ref "TP_GND") (pin "TP") (pinfunction "TP_TP") (pintype "input"))
      (node (ref "TP_GND1") (pin "TP") (pinfunction "TP_TP") (pintype "input"))
      (node (ref "U1") (pin "2") (pinfunction "VSS_2") (pintype "power_in"))
      (node (ref "U2") (pin "1") (pinfunction "GND_1") (pintype "power_in"))
      (node (ref "U2") (pin "28") (pinfunction "GND_28") (pintype "power_in"))
      (node (ref "U2") (pin "29_1") (pinfunction "GND_29_1") (pintype "power_in"))
      (node (ref "U2") (pin "29_2") (pinfunction "GND_29_2") (pintype "power_in"))
      (node (ref "U2") (pin "29_3") (pinfunction "GND_29_3") (pintype "power_in"))
      (node (ref "U2") (pin "29_4") (pinfunction "GND_29_4") (pintype "power_in"))
      (node (ref "U2") (pin "29_5") (pinfunction "GND_29_5") (pintype "power_in"))
      (node (ref "U2") (pin "29_6") (pinfunction "GND_29_6") (pintype "power_in"))
      (node (ref "U2") (pin "29_7") (pinfunction "GND_29_7") (pintype "power_in"))
      (node (ref "U2") (pin "29_8") (pinfunction "GND_29_8") (pintype "power_in"))
      (node (ref "U2") (pin "29_9") (pinfunction "GND_29_9") (pintype "power_in"))
      (node (ref "U4") (pin "1") (pinfunction "CTG_1") (pintype "power_in"))
      (node (ref "U4") (pin "4") (pinfunction "GND_4") (pintype "power_in"))
      (node (ref "U4") (pin "6") (pinfunction "QSTRT_6") (pintype "input"))
      (node (ref "U4") (pin "9") (pinfunction "EP_9") (pintype "power_in"))
      (node (ref "U5") (pin "13") (pinfunction "GND_13") (pintype "power_in"))
      (node (ref "U6") (pin "4") (pinfunction "GND_4") (pintype "power_in"))
      (node (ref "U6") (pin "9") (pinfunction "EXP_9") (pintype "passive"))
    )
    (net (code "15") (name "GPIO8") (class "Default")
      (node (ref "R10") (pin "1") (pinfunction "1_1") (pintype "passive"))
      (node (ref "U2") (pin "10") (pinfunction "IO8_10") (pintype "bidirectional"))
    )
    (net (code "16") (name "I2C_PW") (class "Default")
      (node (ref "C21") (pin "1") (pinfunction "1_1") (pintype "passive"))
      (node (ref "C22") (pin "1") (pinfunction "1_1") (pintype "passive"))
      (node (ref "R12_PINH") (pin "2") (pinfunction "2_2") (pintype "passive"))
      (node (ref "R13_PINH") (pin "2") (pinfunction "2_2") (pintype "passive"))
      (node (ref "SENSOR2") (pin "2") (pinfunction "CSB_2") (pintype "input"))
      (node (ref "SENSOR2") (pin "6") (pinfunction "VDDIO_6") (pintype "power_in"))
      (node (ref "SENSOR2") (pin "8") (pinfunction "VDD_8") (pintype "power_in"))
      (node (ref "U2") (pin "17") (pinfunction "IO19_17") (pintype "bidirectional"))
    )
    (net (code "17") (name "INT_RTC") (class "Default")
      (node (ref "R15_PINH1") (pin "1") (pinfunction "1_1") (pintype "passive"))
      (node (ref "TP_INT_RTC") (pin "TP") (pinfunction "TP_TP") (pintype "input"))
      (node (ref "U2") (pin "8") (pinfunction "IO0_8") (pintype "bidirectional"))
      (node (ref "U5") (pin "3") (pinfunction "SQW/~{INT}_3") (pintype "output"))
    )
    (net (code "18") (name "IO{slash}BOOT") (class "Default")
      (node (ref "BOOT_BUTTON") (pin "3") (pinfunction "3_3") (pintype "passive"))
      (node (ref "BOOT_BUTTON") (pin "4") (pinfunction "4_4") (pintype "passive"))
      (node (ref "C24") (pin "1") (pinfunction "1_1") (pintype "passive"))
      (node (ref "R_BOOT") (pin "1") (pinfunction "1_1") (pintype "passive"))
      (node (ref "U2") (pin "15") (pinfunction "IO9_15") (pintype "bidirectional"))
    )
    (net (code "19") (name "IO{slash}CHANGE") (class "Default")
      (node (ref "C25") (pin "1") (pinfunction "1_1") (pintype "passive"))
      (node (ref "CHANGE_BUTTON") (pin "3") (pinfunction "3_3") (pintype "passive"))
      (node (ref "CHANGE_BUTTON") (pin "4") (pinfunction "4_4") (pintype "passive"))
      (node (ref "R_CHANGE") (pin "1") (pinfunction "1_1") (pintype "passive"))
      (node (ref "U2") (pin "23") (pinfunction "IO15_23") (pintype "bidirectional"))
    )
    (net (code "20") (name "MISO") (class "Default")
      (node (ref "D7") (pin "1") (pinfunction "1_1") (pintype "passive"))
      (node (ref "J2") (pin "P7") (pinfunction "DAT0_P7") (pintype "bidirectional"))
      (node (ref "R16") (pin "1") (pinfunction "1_1") (pintype "passive"))
      (node (ref "TP_MISO") (pin "TP") (pinfunction "TP_TP") (pintype "input"))
      (node (ref "U2") (pin "27") (pinfunction "IO2_27") (pintype "bidirectional"))
      (node (ref "U6") (pin "2") (pinfunction "DO(IO1)_2") (pintype "bidirectional"))
    )
    (net (code "21") (name "MOSI") (class "Default")
      (node (ref "D8") (pin "1") (pinfunction "1_1") (pintype "passive"))
      (node (ref "J2") (pin "P3") (pinfunction "CMD_P3") (pintype "bidirectional"))
      (node (ref "J3") (pin "14") (pinfunction "14_14") (pintype "bidirectional"))
      (node (ref "R17") (pin "1") (pinfunction "1_1") (pintype "passive"))
      (node (ref "TP_MOSI") (pin "TP") (pinfunction "TP_TP") (pintype "input"))
      (node (ref "U2") (pin "7") (pinfunction "IO7_7") (pintype "bidirectional"))
      (node (ref "U6") (pin "5") (pinfunction "DI(IO0)_5") (pintype "bidirectional"))
    )
    (net (code "22") (name "Net-(CHG_LED-PadC)") (class "Default")
      (node (ref "CHG_LED") (pin "C") (pinfunction "C_C") (pintype "passive"))
      (node (ref "R8BAT") (pin "1") (pinfunction "1_1") (pintype "passive"))
    )
    (net (code "23") (name "Net-(D2-CATHODE)") (class "Default")
      (node (ref "C3BAT") (pin "1") (pinfunction "1_1") (pintype "passive"))
      (node (ref "D2") (pin "1") (pinfunction "CATHODE_1") (pintype "bidirectional"))
      (node (ref "IC1") (pin "1") (pinfunction "VIN_1") (pintype "bidirectional"))
      (node (ref "IC1") (pin "3") (pinfunction "CE_3") (pintype "bidirectional"))
      (node (ref "Q1") (pin "2") (pinfunction "S_2") (pintype "bidirectional"))
    )
    (net (code "24") (name "Net-(D4-K)") (class "Default")
      (node (ref "C8") (pin "1") (pinfunction "1_1") (pintype "passive"))
      (node (ref "D4") (pin "1") (pinfunction "K_1") (pintype "bidirectional"))
      (node (ref "D5") (pin "2") (pinfunction "A_2") (pintype "bidirectional"))
    )
    (net (code "25") (name "Net-(D6-CATHODE)") (class "Default")
      (node (ref "D6") (pin "1") (pinfunction "CATHODE_1") (pintype "bidirectional"))
      (node (ref "R_CAPACITOR") (pin "2") (pinfunction "2_2") (pintype "passive"))
    )
    (net (code "26") (name "Net-(EPD_C1-Pad2)") (class "Default")
      (node (ref "EPD_C1") (pin "2") (pinfunction "2_2") (pintype "passive"))
      (node (ref "J3") (pin "4") (pinfunction "4_4") (pintype "bidirectional"))
    )
    (net (code "27") (name "Net-(EPD_C2-Pad2)") (class "Default")
      (node (ref "EPD_C2") (pin "2") (pinfunction "2_2") (pintype "passive"))
      (node (ref "J3") (pin "5") (pinfunction "5_5") (pintype "bidirectional"))
    )
    (net (code "28") (name "Net-(EPD_C6-Pad2)") (class "Default")
      (node (ref "EPD_C6") (pin "2") (pinfunction "2_2") (pintype "passive"))
      (node (ref "J3") (pin "18") (pinfunction "18_18") (pintype "bidirectional"))
    )
    (net (code "29") (name "Net-(EPD_C7-Pad2)") (class "Default")
      (node (ref "EPD_C7") (pin "2") (pinfunction "2_2") (pintype "passive"))
      (node (ref "J3") (pin "19") (pinfunction "19_19") (pintype "bidirectional"))
    )
    (net (code "30") (name "Net-(EPD_C8-Pad2)") (class "Default")
      (node (ref "EPD_C8") (pin "2") (pinfunction "2_2") (pintype "passive"))
      (node (ref "J3") (pin "20") (pinfunction "20_20") (pintype "bidirectional"))
    )
    (net (code "31") (name "Net-(EPD_C10-Pad2)") (class "Default")
      (node (ref "EPD_C10") (pin "2") (pinfunction "2_2") (pintype "passive"))
      (node (ref "J3") (pin "22") (pinfunction "22_22") (pintype "bidirectional"))
    )
    (net (code "32") (name "Net-(EPD_C12-Pad2)") (class "Default")
      (node (ref "EPD_C12") (pin "2") (pinfunction "2_2") (pintype "passive"))
      (node (ref "J3") (pin "24") (pinfunction "24_24") (pintype "bidirectional"))
    )
    (net (code "33") (name "Net-(IC2-CT)") (class "Default")
      (node (ref "C_DELAY") (pin "1") (pinfunction "1_1") (pintype "passive"))
      (node (ref "IC2") (pin "5") (pinfunction "CT_5") (pintype "bidirectional"))
    )
    (net (code "34") (name "Net-(J1-PadA5)") (class "Default")
      (node (ref "J1") (pin "A5") (pinfunction "A5_A5") (pintype "bidirectional"))
      (node (ref "R2USB") (pin "2") (pinfunction "2_2") (pintype "passive"))
    )
    (net (code "35") (name "Net-(J1-PadB5)") (class "Default")
      (node (ref "J1") (pin "B5") (pinfunction "B5_B5") (pintype "bidirectional"))
      (node (ref "R3USB1") (pin "1") (pinfunction "1_1") (pintype "passive"))
    )
    (net (code "36") (name "Net-(U1-PROG)") (class "Default")
      (node (ref "R9BAT") (pin "2") (pinfunction "2_2") (pintype "passive"))
      (node (ref "U1") (pin "5") (pinfunction "PROG_5") (pintype "input"))
    )
    (net (code "37") (name "Net-(U1-STAT)") (class "Default")
      (node (ref "R8BAT") (pin "2") (pinfunction "2_2") (pintype "passive"))
      (node (ref "U1") (pin "1") (pinfunction "STAT_1") (pintype "output"))
    )
    (net (code "38") (name "PREVGH") (class "Default")
      (node (ref "D3") (pin "1") (pinfunction "K_1") (pintype "bidirectional"))
      (node (ref "EPD_C9") (pin "2") (pinfunction "2_2") (pintype "passive"))
      (node (ref "J3") (pin "21") (pinfunction "21_21") (pintype "bidirectional"))
    )
    (net (code "39") (name "PREVGL") (class "Default")
      (node (ref "D4") (pin "2") (pinfunction "A_2") (pintype "bidirectional"))
      (node (ref "EPD_C11") (pin "2") (pinfunction "2_2") (pintype "passive"))
      (node (ref "J3") (pin "23") (pinfunction "23_23") (pintype "bidirectional"))
    )
    (net (code "40") (name "RESE") (class "Default")
      (node (ref "J3") (pin "3") (pinfunction "3_3") (pintype "bidirectional"))
      (node (ref "Q2") (pin "2") (pinfunction "S_2") (pintype "bidirectional"))
      (node (ref "R7") (pin "2") (pinfunction "2_2") (pintype "passive"))
    )
    (net (code "41") (name "RESE'") (class "Default")
      (node (ref "R5") (pin "2") (pinfunction "2_2") (pintype "passive"))
      (node (ref "R7") (pin "1") (pinfunction "1_1") (pintype "passive"))
      (node (ref "SJ1") (pin "2") (pinfunction "2_2") (pintype "passive"))
    )
    (net (code "42") (name "RESET") (class "Default")
      (node (ref "C23") (pin "1") (pinfunction "1_1") (pintype "passive"))
      (node (ref "IC2") (pin "1") (pinfunction "VOUT_1") (pintype "bidirectional"))
      (node (ref "RESET_BUTTON") (pin "3") (pinfunction "3_3") (pintype "passive"))
      (node (ref "RESET_BUTTON") (pin "4") (pinfunction "4_4") (pintype "passive"))
      (node (ref "R_RESET") (pin "1") (pinfunction "1_1") (pintype "passive"))
      (node (ref "U2") (pin "3") (pinfunction "EN_3") (pintype "input"))
    )
    (net (code "43") (name "RTC_RST") (class "Default")
      (node (ref "U2") (pin "16") (pinfunction "IO18_16") (pintype "bidirectional"))
      (node (ref "U5") (pin "4") (pinfunction "~{RST}_4") (pintype "input"))
    )
    (net (code "44") (name "RX") (class "Default")
      (node (ref "TP_RX") (pin "TP") (pinfunction "TP_TP") (pintype "input"))
      (node (ref "U2") (pin "24") (pinfunction "RXD0/GPIO17_24") (pintype "bidirectional"))
    )
    (net (code "45") (name "SCK") (class "Default")
      (node (ref "D9") (pin "1") (pinfunction "1_1") (pintype "passive"))
      (node (ref "J2") (pin "P5") (pinfunction "CLK_P5") (pintype "bidirectional"))
      (node (ref "J3") (pin "13") (pinfunction "13_13") (pintype "bidirectional"))
      (node (ref "R18") (pin "1") (pinfunction "1_1") (pintype "passive"))
      (node (ref "TP_SCK") (pin "TP") (pinfunction "TP_TP") (pintype "input"))
      (node (ref "U2") (pin "6") (pinfunction "IO6_6") (pintype "bidirectional"))
      (node (ref "U6") (pin "6") (pinfunction "CLK_6") (pintype "input"))
    )
    (net (code "46") (name "SCL") (class "Default")
      (node (ref "J4") (pin "4") (pinfunction "4_4") (pintype "passive"))
      (node (ref "R12_PINH") (pin "1") (pinfunction "1_1") (pintype "passive"))
      (node (ref "SENSOR2") (pin "4") (pinfunction "SCK_4") (pintype "input"))
      (node (ref "U2") (pin "20") (pinfunction "IO22_20") (pintype "bidirectional"))
      (node (ref "U4") (pin "7") (pinfunction "SCL_7") (pintype "input"))
      (node (ref "U5") (pin "16") (pinfunction "SCL_16") (pintype "input"))
    )
    (net (code "47") (name "SDA") (class "Default")
      (node (ref "J4") (pin "3") (pinfunction "3_3") (pintype "passive"))
      (node (ref "R13_PINH") (pin "1") (pinfunction "1_1") (pintype "passive"))
      (node (ref "SENSOR2") (pin "3") (pinfunction "SDI_3") (pintype "bidirectional"))
      (node (ref "U2") (pin "19") (pinfunction "IO21_19") (pintype "bidirectional"))
      (node (ref "U4") (pin "8") (pinfunction "SDA_8") (pintype "bidirectional"))
      (node (ref "U5") (pin "15") (pinfunction "SDA_15") (pintype "bidirectional"))
    )
    (net (code "48") (name "SRC") (class "Default")
      (node (ref "C8") (pin "2") (pinfunction "2_2") (pintype "passive"))
      (node (ref "D3") (pin "2") (pinfunction "A_2") (pintype "bidirectional"))
      (node (ref "L2") (pin "1") (pinfunction "1_1") (pintype "passive"))
      (node (ref "Q2") (pin "3") (pinfunction "D_3") (pintype "bidirectional"))
    )
    (net (code "49") (name "SS_SD") (class "Default")
      (node (ref "D12") (pin "1") (pinfunction "1_1") (pintype "passive"))
      (node (ref "J2") (pin "P2") (pinfunction "CD/DAT3_P2") (pintype "bidirectional"))
      (node (ref "R21") (pin "1") (pinfunction "1_1") (pintype "passive"))
      (node (ref "U2") (pin "4") (pinfunction "IO4_4") (pintype "bidirectional"))
    )
    (net (code "50") (name "TX") (class "Default")
      (node (ref "TP_TX") (pin "TP") (pinfunction "TP_TP") (pintype "input"))
      (node (ref "U2") (pin "25") (pinfunction "TXD0/GPIO16_25") (pintype "bidirectional"))
    )
    (net (code "51") (name "USB_D+") (class "Default")
      (node (ref "D1") (pin "1") (pinfunction "I/O1_1_1") (pintype "bidirectional"))
      (node (ref "U2") (pin "14") (pinfunction "IO13_14") (pintype "bidirectional"))
    )
    (net (code "52") (name "USB_D-") (class "Default")
      (node (ref "D1") (pin "3") (pinfunction "I/O2_1_3") (pintype "bidirectional"))
      (node (ref "U2") (pin "13") (pinfunction "IO12_13") (pintype "bidirectional"))
    )
    (net (code "53") (name "VBAT") (class "Default")
      (node (ref "C10BAT") (pin "1") (pinfunction "1_1") (pintype "passive"))
      (node (ref "Q1") (pin "3") (pinfunction "D_3") (pintype "bidirectional"))
      (node (ref "TP_VBAT") (pin "TP") (pinfunction "TP_TP") (pintype "input"))
      (node (ref "U1") (pin "3") (pinfunction "VBAT_3") (pintype "power_in"))
      (node (ref "U4") (pin "2") (pinfunction "CELL_2") (pintype "power_in"))
      (node (ref "U4") (pin "3") (pinfunction "VDD_3") (pintype "power_in"))
    )
    (net (code "54") (name "VBUS") (class "Default")
      (node (ref "C1USB") (pin "1") (pinfunction "1_1") (pintype "passive"))
      (node (ref "C2USB1") (pin "1") (pinfunction "1_1") (pintype "passive"))
      (node (ref "C9BAT") (pin "1") (pinfunction "1_1") (pintype "passive"))
      (node (ref "CHG_LED") (pin "A") (pinfunction "A_A") (pintype "passive"))
      (node (ref "D1") (pin "5") (pinfunction "VBUS_5") (pintype "bidirectional"))
      (node (ref "D2") (pin "2") (pinfunction "ANODE_2") (pintype "bidirectional"))
      (node (ref "Q1") (pin "1") (pinfunction "G_1") (pintype "bidirectional"))
      (node (ref "R1") (pin "2") (pinfunction "2_2") (pintype "passive"))
      (node (ref "R4PWRUSB1") (pin "2") (pinfunction "2_2") (pintype "passive"))
      (node (ref "TP_VBUS") (pin "TP") (pinfunction "TP_TP") (pintype "input"))
      (node (ref "U1") (pin "4") (pinfunction "VIN_4") (pintype "power_in"))
    )
    (net (code "55") (name "VRTC") (class "Default")
      (node (ref "C26") (pin "1") (pinfunction "1_1") (pintype "passive"))
      (node (ref "R_CAPACITOR") (pin "1") (pinfunction "1_1") (pintype "passive"))
      (node (ref "SUPERCAP") (pin "1") (pinfunction "1_1") (pintype "passive"))
      (node (ref "U5") (pin "14") (pinfunction "VBAT_14") (pintype "power_in"))
    )
    (net (code "56") (name "unconnected-(IC1-NC-Pad4)") (class "Default")
      (node (ref "IC1") (pin "4") (pinfunction "NC_4") (pintype "no_connect"))
    )
    (net (code "57") (name "unconnected-(IC2-NC-Pad4)") (class "Default")
      (node (ref "IC2") (pin "4") (pinfunction "NC_4") (pintype "no_connect"))
    )
    (net (code "58") (name "unconnected-(J1-PadA8)") (class "Default")
      (node (ref "J1") (pin "A8") (pinfunction "A8_A8") (pintype "bidirectional"))
    )
    (net (code "59") (name "unconnected-(J1-PadB8)") (class "Default")
      (node (ref "J1") (pin "B8") (pinfunction "B8_B8") (pintype "bidirectional"))
    )
    (net (code "60") (name "unconnected-(J2-DAT1-PadP8)") (class "Default")
      (node (ref "J2") (pin "P8") (pinfunction "DAT1_P8") (pintype "bidirectional"))
    )
    (net (code "61") (name "unconnected-(J2-DAT2-PadP1)") (class "Default")
      (node (ref "J2") (pin "P1") (pinfunction "DAT2_P1") (pintype "bidirectional"))
    )
    (net (code "62") (name "unconnected-(J2-DETECTION_1-PadS1)") (class "Default")
      (node (ref "J2") (pin "S1") (pinfunction "DETECTION_1_S1") (pintype "bidirectional"))
    )
    (net (code "63") (name "unconnected-(J2-DETECTION_2-PadS2)") (class "Default")
      (node (ref "J2") (pin "S2") (pinfunction "DETECTION_2_S2") (pintype "bidirectional"))
    )
    (net (code "64") (name "unconnected-(J3-Pad1)") (class "Default")
      (node (ref "J3") (pin "1") (pinfunction "1_1") (pintype "bidirectional"))
    )
    (net (code "65") (name "unconnected-(J3-Pad6)") (class "Default")
      (node (ref "J3") (pin "6") (pinfunction "6_6") (pintype "bidirectional"))
    )
    (net (code "66") (name "unconnected-(J3-Pad7)") (class "Default")
      (node (ref "J3") (pin "7") (pinfunction "7_7") (pintype "bidirectional"))
    )
    (net (code "67") (name "unconnected-(U2-NC-Pad22)") (class "Default")
      (node (ref "U2") (pin "22") (pinfunction "NC_22") (pintype "no_connect"))
    )
    (net (code "68") (name "unconnected-(U4-~{ALERT}-Pad5)") (class "Default")
      (node (ref "U4") (pin "5") (pinfunction "~{ALERT}_5") (pintype "output"))
    )
  )
)
